# 2022-4T-MNT-4.net
KiCad netlist of a schematic drawn in EasyEDA Pro
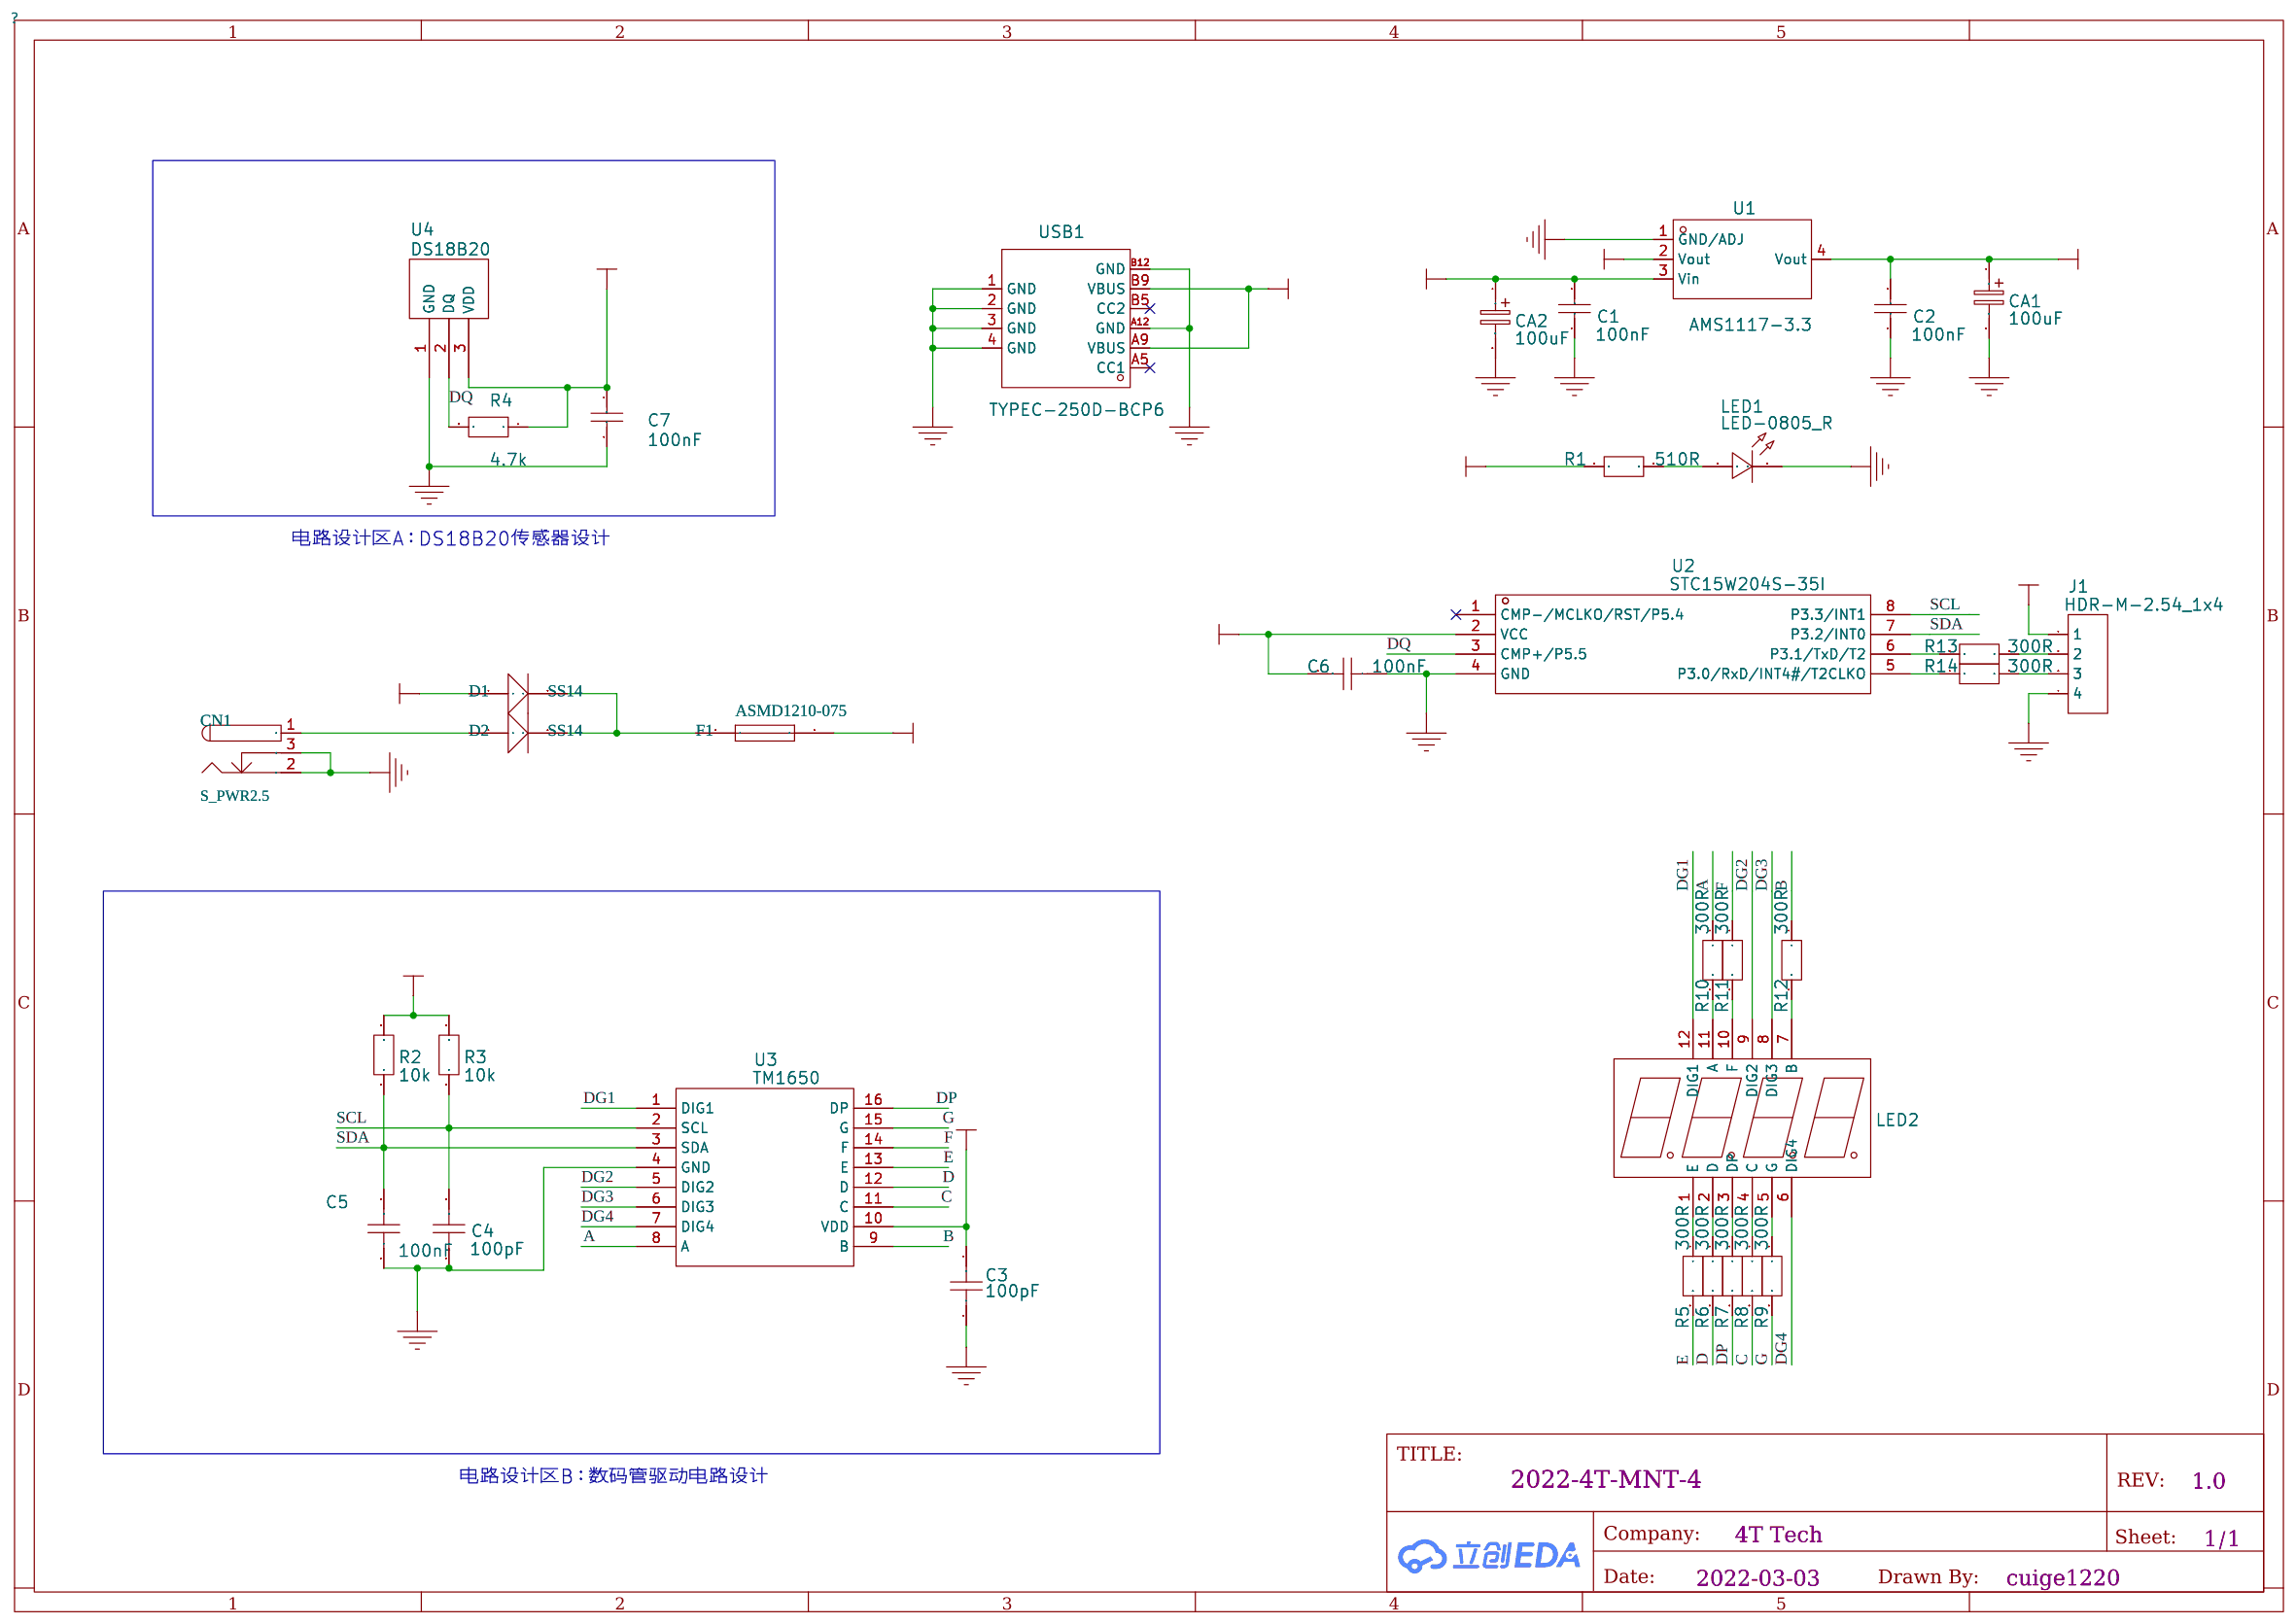
[diagram p0: schematic sheet]

(export (version "E")
  (design (tool "Eeschema 10.0.6"))
  (components
    (comp (ref "C1")
      (value "100nF")
      (fields (field (name "Manufacturer Part") "0805F104M500NT") (field (name "Manufacturer") "FH"))
      (libsource (lib "") (part "100nF_1"))
    )
    (comp (ref "C2")
      (value "100nF")
      (fields (field (name "Manufacturer Part") "0805F104M500NT") (field (name "Manufacturer") "FH"))
      (libsource (lib "") (part "100nF_1"))
    )
    (comp (ref "C3") (value "100pF") (libsource (lib "easyedapro") (part "100pF")))
    (comp (ref "C4") (value "100pF") (libsource (lib "easyedapro") (part "100pF")))
    (comp (ref "C5") (value "100nF") (libsource (lib "easyedapro") (part "100nF")))
    (comp (ref "C6") (value "100nF") (libsource (lib "easyedapro") (part "100nF")))
    (comp (ref "C7")
      (value "100nF")
      (fields (field (name "Manufacturer Part") "0805F104M500NT") (field (name "Manufacturer") "FH"))
      (libsource (lib "") (part "100nF_1"))
    )
    (comp (ref "CA1") (value "100uF") (libsource (lib "easyedapro") (part "100uF")))
    (comp (ref "CA2") (value "100uF") (libsource (lib "easyedapro") (part "100uF")))
    (comp (ref "CN1") (value "S_PWR2.5") (libsource (lib "easyedapro") (part "S_PWR2.5")))
    (comp (ref "D1")
      (value "SS14")
      (fields (field (name "Publisher") "Altium Limited"))
      (libsource (lib "easyedapro") (part "SS14"))
    )
    (comp (ref "D2")
      (value "SS14")
      (fields (field (name "Publisher") "Altium Limited"))
      (libsource (lib "easyedapro") (part "SS14"))
    )
    (comp (ref "F1")
      (value "ASMD1210-075")
      (fields (field (name "Publisher") "Altium Limited"))
      (libsource (lib "easyedapro") (part "ASMD1210-075"))
    )
    (comp (ref "J1") (value "HDR-M-2.54_1x4") (libsource (lib "easyedapro") (part "HDR-M-2.54_1x4")))
    (comp (ref "LED1")
      (value "LED-0805_R")
      (fields
        (field (name "Manufacturer Part") "17-21SURC/S530-A3/TR8")
        (field (name "Manufacturer") "EVERLIGHT(台湾亿光)")
      )
      (libsource (lib "easyedapro") (part "LED-0805_R"))
    )
    (comp (ref "LED2")
      (value "DSP")
      (fields
        (field (name "Manufacturer Part") "SR420361N")
        (field (name "Manufacturer") "Wuxi ARK Tech Elec")
      )
      (libsource (lib "easyedapro") (part "DSP"))
    )
    (comp (ref "R1") (value "510R") (libsource (lib "easyedapro") (part "510R")))
    (comp (ref "R2") (value "10k") (libsource (lib "easyedapro") (part "10k")))
    (comp (ref "R3") (value "10k") (libsource (lib "easyedapro") (part "10k")))
    (comp (ref "R4") (value "4.7k") (libsource (lib "easyedapro") (part "4.7k")))
    (comp (ref "R5") (value "300R") (libsource (lib "easyedapro") (part "300R")))
    (comp (ref "R6") (value "300R") (libsource (lib "easyedapro") (part "300R")))
    (comp (ref "R7") (value "300R") (libsource (lib "easyedapro") (part "300R")))
    (comp (ref "R8") (value "300R") (libsource (lib "easyedapro") (part "300R")))
    (comp (ref "R9") (value "300R") (libsource (lib "easyedapro") (part "300R")))
    (comp (ref "R10") (value "300R") (libsource (lib "easyedapro") (part "300R")))
    (comp (ref "R11") (value "300R") (libsource (lib "easyedapro") (part "300R")))
    (comp (ref "R12") (value "300R") (libsource (lib "easyedapro") (part "300R")))
    (comp (ref "R13") (value "300R") (libsource (lib "easyedapro") (part "300R")))
    (comp (ref "R14") (value "300R") (libsource (lib "easyedapro") (part "300R")))
    (comp (ref "U1")
      (value "AMS1117-3.3")
      (fields (field (name "Manufacturer") "AMS"))
      (libsource (lib "easyedapro") (part "AMS1117-3.3"))
    )
    (comp (ref "U2")
      (value "STC15W204S-35I")
      (fields (field (name "Manufacturer") "STC"))
      (libsource (lib "easyedapro") (part "STC15W204S-35I"))
    )
    (comp (ref "U3")
      (value "TM1650")
      (fields (field (name "Manufacturer") "TM"))
      (libsource (lib "easyedapro") (part "TM1650"))
    )
    (comp (ref "U4") (value "DS18B20") (libsource (lib "easyedapro") (part "DS18B20")))
    (comp (ref "USB1")
      (value "TYPEC-250D-BCP6")
      (fields (field (name "Manufacturer") "XUNPU"))
      (libsource (lib "easyedapro") (part "TYPEC-250D-BCP6"))
    )
  )
  (nets
    (net (code "1") (name "+5V0") (class "Default")
      (node (ref "C1") (pin "2") (pinfunction "2_2") (pintype "input"))
      (node (ref "CA2") (pin "1") (pinfunction "1_1") (pintype "input"))
      (node (ref "F1") (pin "2") (pinfunction "2_2") (pintype "input"))
      (node (ref "U1") (pin "3") (pinfunction "Vin_3") (pintype "input"))
    )
    (net (code "2") (name "/A") (class "Default")
      (node (ref "R10") (pin "1") (pinfunction "1_1") (pintype "input"))
      (node (ref "U3") (pin "8") (pinfunction "A_8") (pintype "input"))
    )
    (net (code "3") (name "/B") (class "Default")
      (node (ref "R12") (pin "1") (pinfunction "1_1") (pintype "input"))
      (node (ref "U3") (pin "9") (pinfunction "B_9") (pintype "input"))
    )
    (net (code "4") (name "/C") (class "Default")
      (node (ref "R8") (pin "2") (pinfunction "2_2") (pintype "input"))
      (node (ref "U3") (pin "11") (pinfunction "C_11") (pintype "input"))
    )
    (net (code "5") (name "/D") (class "Default")
      (node (ref "R6") (pin "2") (pinfunction "2_2") (pintype "input"))
      (node (ref "U3") (pin "12") (pinfunction "D_12") (pintype "input"))
    )
    (net (code "6") (name "/DG1") (class "Default")
      (node (ref "LED2") (pin "12") (pinfunction "DIG1_12") (pintype "input"))
      (node (ref "U3") (pin "1") (pinfunction "DIG1_1") (pintype "input"))
    )
    (net (code "7") (name "/DG2") (class "Default")
      (node (ref "LED2") (pin "9") (pinfunction "DIG2_9") (pintype "input"))
      (node (ref "U3") (pin "5") (pinfunction "DIG2_5") (pintype "input"))
    )
    (net (code "8") (name "/DG3") (class "Default")
      (node (ref "LED2") (pin "8") (pinfunction "DIG3_8") (pintype "input"))
      (node (ref "U3") (pin "6") (pinfunction "DIG3_6") (pintype "input"))
    )
    (net (code "9") (name "/DG4") (class "Default")
      (node (ref "LED2") (pin "6") (pinfunction "DIG4_6") (pintype "input"))
      (node (ref "U3") (pin "7") (pinfunction "DIG4_7") (pintype "input"))
    )
    (net (code "10") (name "/DP") (class "Default")
      (node (ref "R7") (pin "2") (pinfunction "2_2") (pintype "input"))
      (node (ref "U3") (pin "16") (pinfunction "DP_16") (pintype "input"))
    )
    (net (code "11") (name "/DQ") (class "Default")
      (node (ref "R4") (pin "2") (pinfunction "2_2") (pintype "input"))
      (node (ref "U2") (pin "3") (pinfunction "CMP+/P5.5_3") (pintype "input"))
      (node (ref "U4") (pin "2") (pinfunction "DQ_2") (pintype "input"))
    )
    (net (code "12") (name "/E") (class "Default")
      (node (ref "R5") (pin "2") (pinfunction "2_2") (pintype "input"))
      (node (ref "U3") (pin "13") (pinfunction "E_13") (pintype "input"))
    )
    (net (code "13") (name "/F") (class "Default")
      (node (ref "R11") (pin "1") (pinfunction "1_1") (pintype "input"))
      (node (ref "U3") (pin "14") (pinfunction "F_14") (pintype "input"))
    )
    (net (code "14") (name "/G") (class "Default")
      (node (ref "R9") (pin "2") (pinfunction "2_2") (pintype "input"))
      (node (ref "U3") (pin "15") (pinfunction "G_15") (pintype "input"))
    )
    (net (code "15") (name "/SCL") (class "Default")
      (node (ref "C4") (pin "2") (pinfunction "2_2") (pintype "input"))
      (node (ref "R3") (pin "1") (pinfunction "1_1") (pintype "input"))
      (node (ref "U2") (pin "8") (pinfunction "P3.3/INT1_8") (pintype "input"))
      (node (ref "U3") (pin "2") (pinfunction "SCL_2") (pintype "input"))
    )
    (net (code "16") (name "/SDA") (class "Default")
      (node (ref "C5") (pin "2") (pinfunction "2_2") (pintype "input"))
      (node (ref "R2") (pin "1") (pinfunction "1_1") (pintype "input"))
      (node (ref "U2") (pin "7") (pinfunction "P3.2/INT0_7") (pintype "input"))
      (node (ref "U3") (pin "3") (pinfunction "SDA_3") (pintype "input"))
    )
    (net (code "17") (name "GND") (class "Default")
      (node (ref "C1") (pin "1") (pinfunction "1_1") (pintype "input"))
      (node (ref "C2") (pin "1") (pinfunction "1_1") (pintype "input"))
      (node (ref "C3") (pin "2") (pinfunction "2_2") (pintype "input"))
      (node (ref "C4") (pin "1") (pinfunction "1_1") (pintype "input"))
      (node (ref "C5") (pin "1") (pinfunction "1_1") (pintype "input"))
      (node (ref "C6") (pin "1") (pinfunction "1_1") (pintype "input"))
      (node (ref "C7") (pin "2") (pinfunction "2_2") (pintype "input"))
      (node (ref "CA1") (pin "2") (pinfunction "2_2") (pintype "input"))
      (node (ref "CA2") (pin "2") (pinfunction "2_2") (pintype "input"))
      (node (ref "CN1") (pin "2") (pinfunction "2_2") (pintype "input"))
      (node (ref "CN1") (pin "3") (pinfunction "3_3") (pintype "input"))
      (node (ref "J1") (pin "4") (pinfunction "4_4") (pintype "input"))
      (node (ref "LED1") (pin "2") (pinfunction "2_2") (pintype "input"))
      (node (ref "U1") (pin "1") (pinfunction "GND/ADJ_1") (pintype "input"))
      (node (ref "U2") (pin "4") (pinfunction "GND_4") (pintype "input"))
      (node (ref "U3") (pin "4") (pinfunction "GND_4") (pintype "input"))
      (node (ref "U4") (pin "1") (pinfunction "GND_1") (pintype "input"))
      (node (ref "USB1") (pin "1") (pinfunction "GND_1") (pintype "input"))
      (node (ref "USB1") (pin "2") (pinfunction "GND_2") (pintype "input"))
      (node (ref "USB1") (pin "3") (pinfunction "GND_3") (pintype "input"))
      (node (ref "USB1") (pin "4") (pinfunction "GND_4") (pintype "input"))
      (node (ref "USB1") (pin "A12") (pinfunction "GND_A12") (pintype "input"))
      (node (ref "USB1") (pin "B12") (pinfunction "GND_B12") (pintype "input"))
    )
    (net (code "18") (name "Net-(D1-K)") (class "Default")
      (node (ref "D1") (pin "2") (pinfunction "K_2") (pintype "input"))
      (node (ref "D2") (pin "2") (pinfunction "K_2") (pintype "input"))
      (node (ref "F1") (pin "1") (pinfunction "1_1") (pintype "input"))
    )
    (net (code "19") (name "Net-(D2-A)") (class "Default")
      (node (ref "CN1") (pin "1") (pinfunction "1_1") (pintype "input"))
      (node (ref "D2") (pin "1") (pinfunction "A_1") (pintype "input"))
    )
    (net (code "20") (name "Net-(J1-Pad2)") (class "Default")
      (node (ref "J1") (pin "2") (pinfunction "2_2") (pintype "input"))
      (node (ref "R13") (pin "2") (pinfunction "2_2") (pintype "input"))
    )
    (net (code "21") (name "Net-(J1-Pad3)") (class "Default")
      (node (ref "J1") (pin "3") (pinfunction "3_3") (pintype "input"))
      (node (ref "R14") (pin "2") (pinfunction "2_2") (pintype "input"))
    )
    (net (code "22") (name "Net-(LED1-Pad1)") (class "Default")
      (node (ref "LED1") (pin "1") (pinfunction "1_1") (pintype "input"))
      (node (ref "R1") (pin "2") (pinfunction "2_2") (pintype "input"))
    )
    (net (code "23") (name "Net-(LED2-A)") (class "Default")
      (node (ref "LED2") (pin "11") (pinfunction "A_11") (pintype "input"))
      (node (ref "R10") (pin "2") (pinfunction "2_2") (pintype "input"))
    )
    (net (code "24") (name "Net-(LED2-B)") (class "Default")
      (node (ref "LED2") (pin "7") (pinfunction "B_7") (pintype "input"))
      (node (ref "R12") (pin "2") (pinfunction "2_2") (pintype "input"))
    )
    (net (code "25") (name "Net-(LED2-C)") (class "Default")
      (node (ref "LED2") (pin "4") (pinfunction "C_4") (pintype "input"))
      (node (ref "R8") (pin "1") (pinfunction "1_1") (pintype "input"))
    )
    (net (code "26") (name "Net-(LED2-D)") (class "Default")
      (node (ref "LED2") (pin "2") (pinfunction "D_2") (pintype "input"))
      (node (ref "R6") (pin "1") (pinfunction "1_1") (pintype "input"))
    )
    (net (code "27") (name "Net-(LED2-DP)") (class "Default")
      (node (ref "LED2") (pin "3") (pinfunction "DP_3") (pintype "input"))
      (node (ref "R7") (pin "1") (pinfunction "1_1") (pintype "input"))
    )
    (net (code "28") (name "Net-(LED2-E)") (class "Default")
      (node (ref "LED2") (pin "1") (pinfunction "E_1") (pintype "input"))
      (node (ref "R5") (pin "1") (pinfunction "1_1") (pintype "input"))
    )
    (net (code "29") (name "Net-(LED2-F)") (class "Default")
      (node (ref "LED2") (pin "10") (pinfunction "F_10") (pintype "input"))
      (node (ref "R11") (pin "2") (pinfunction "2_2") (pintype "input"))
    )
    (net (code "30") (name "Net-(LED2-G)") (class "Default")
      (node (ref "LED2") (pin "5") (pinfunction "G_5") (pintype "input"))
      (node (ref "R9") (pin "1") (pinfunction "1_1") (pintype "input"))
    )
    (net (code "31") (name "Net-(U2-P3.0{slash}RxD{slash}INT4#{slash}T2CLKO)") (class "Default")
      (node (ref "R14") (pin "1") (pinfunction "1_1") (pintype "input"))
      (node (ref "U2") (pin "5") (pinfunction "P3.0/RxD/INT4#/T2CLKO_5") (pintype "input"))
    )
    (net (code "32") (name "Net-(U2-P3.1{slash}TxD{slash}T2)") (class "Default")
      (node (ref "R13") (pin "1") (pinfunction "1_1") (pintype "input"))
      (node (ref "U2") (pin "6") (pinfunction "P3.1/TxD/T2_6") (pintype "input"))
    )
    (net (code "33") (name "VDD") (class "Default")
      (node (ref "C2") (pin "2") (pinfunction "2_2") (pintype "input"))
      (node (ref "C3") (pin "1") (pinfunction "1_1") (pintype "input"))
      (node (ref "C6") (pin "2") (pinfunction "2_2") (pintype "input"))
      (node (ref "C7") (pin "1") (pinfunction "1_1") (pintype "input"))
      (node (ref "CA1") (pin "1") (pinfunction "1_1") (pintype "input"))
      (node (ref "J1") (pin "1") (pinfunction "1_1") (pintype "input"))
      (node (ref "R1") (pin "1") (pinfunction "1_1") (pintype "input"))
      (node (ref "R2") (pin "2") (pinfunction "2_2") (pintype "input"))
      (node (ref "R3") (pin "2") (pinfunction "2_2") (pintype "input"))
      (node (ref "R4") (pin "1") (pinfunction "1_1") (pintype "input"))
      (node (ref "U1") (pin "2") (pinfunction "Vout_2") (pintype "input"))
      (node (ref "U1") (pin "4") (pinfunction "Vout_4") (pintype "input"))
      (node (ref "U2") (pin "2") (pinfunction "VCC_2") (pintype "input"))
      (node (ref "U3") (pin "10") (pinfunction "VDD_10") (pintype "input"))
      (node (ref "U4") (pin "3") (pinfunction "VDD_3") (pintype "input"))
    )
    (net (code "34") (name "VUSB") (class "Default")
      (node (ref "D1") (pin "1") (pinfunction "A_1") (pintype "input"))
      (node (ref "USB1") (pin "A9") (pinfunction "VBUS_A9") (pintype "input"))
      (node (ref "USB1") (pin "B9") (pinfunction "VBUS_B9") (pintype "input"))
    )
    (net (code "35") (name "unconnected-(U2-CMP-{slash}MCLKO{slash}RST{slash}P5.4-Pad1)") (class "Default")
      (node (ref "U2") (pin "1") (pinfunction "CMP-/MCLKO/RST/P5.4_1") (pintype "input+no_connect"))
    )
    (net (code "36") (name "unconnected-(USB1-CC1-PadA5)") (class "Default")
      (node (ref "USB1") (pin "A5") (pinfunction "CC1_A5") (pintype "input+no_connect"))
    )
    (net (code "37") (name "unconnected-(USB1-CC2-PadB5)") (class "Default")
      (node (ref "USB1") (pin "B5") (pinfunction "CC2_B5") (pintype "input+no_connect"))
    )
  )
)
